# GD32FxxxR-dev-board.net
KiCad netlist of a schematic drawn in EAGLE
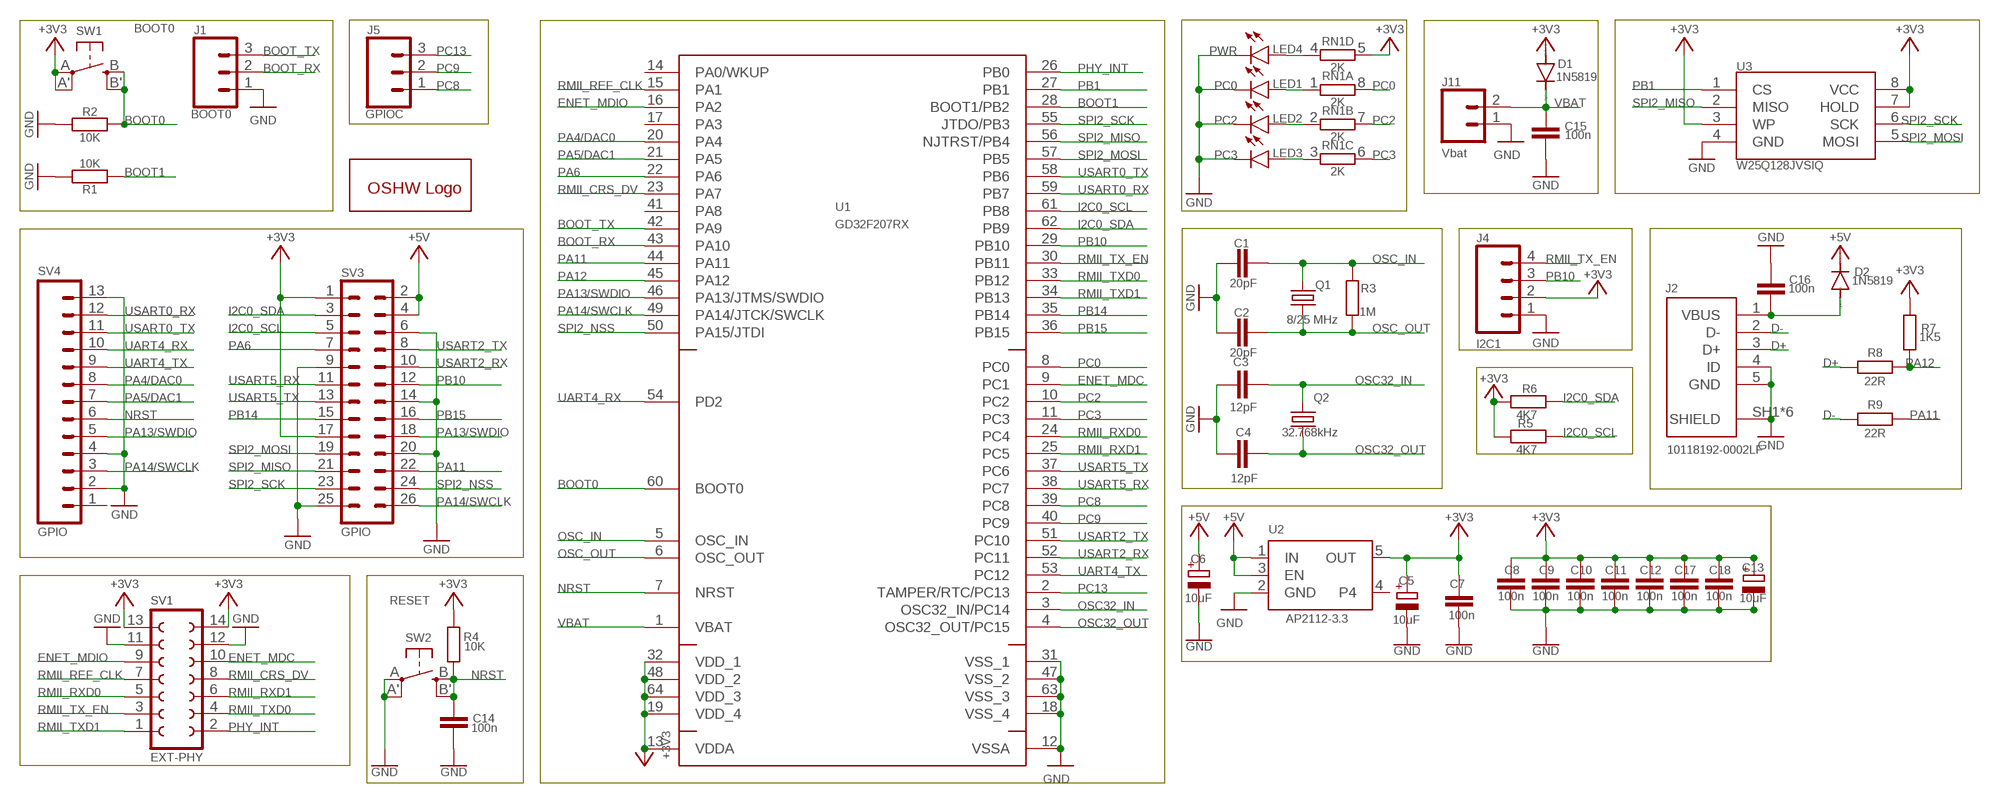
[diagram p0: schematic, sheet 1]

(export (version "E")
  (design (tool "Eeschema 10.0.6"))
  (components
    (comp (ref "C1")
      (value "20pF")
      (footprint "eagle-import:C0603")
      (libsource (lib "eagle-import") (part "C-EUC0603"))
    )
    (comp (ref "C2")
      (value "20pF")
      (footprint "eagle-import:C0603")
      (libsource (lib "eagle-import") (part "C-EUC0603"))
    )
    (comp (ref "C3")
      (value "12pF")
      (footprint "eagle-import:C0603")
      (libsource (lib "eagle-import") (part "C-EUC0603"))
    )
    (comp (ref "C4")
      (value "12pF")
      (footprint "eagle-import:C0603")
      (libsource (lib "eagle-import") (part "C-EUC0603"))
    )
    (comp (ref "C5")
      (value "10uF")
      (footprint "eagle-import:A_3216-18R")
      (libsource (lib "eagle-import") (part "CPOL-EUA/3216-18R"))
    )
    (comp (ref "C6")
      (value "10uF")
      (footprint "eagle-import:A_3216-18R")
      (libsource (lib "eagle-import") (part "CPOL-EUA/3216-18R"))
    )
    (comp (ref "C7")
      (value "100n")
      (footprint "eagle-import:C0603")
      (libsource (lib "eagle-import") (part "C-EUC0603"))
    )
    (comp (ref "C8")
      (value "100n")
      (footprint "eagle-import:C0603")
      (libsource (lib "eagle-import") (part "C-EUC0603"))
    )
    (comp (ref "C9")
      (value "100n")
      (footprint "eagle-import:C0603")
      (libsource (lib "eagle-import") (part "C-EUC0603"))
    )
    (comp (ref "C10")
      (value "100n")
      (footprint "eagle-import:C0603")
      (libsource (lib "eagle-import") (part "C-EUC0603"))
    )
    (comp (ref "C11")
      (value "100n")
      (footprint "eagle-import:C0603")
      (libsource (lib "eagle-import") (part "C-EUC0603"))
    )
    (comp (ref "C12")
      (value "100n")
      (footprint "eagle-import:C0603")
      (libsource (lib "eagle-import") (part "C-EUC0603"))
    )
    (comp (ref "C13")
      (value "10uF")
      (footprint "eagle-import:A_3216-18R")
      (libsource (lib "eagle-import") (part "CPOL-EUA/3216-18R"))
    )
    (comp (ref "C14")
      (value "100n")
      (footprint "eagle-import:C0603")
      (libsource (lib "eagle-import") (part "C-EUC0603"))
    )
    (comp (ref "C15")
      (value "100n")
      (footprint "eagle-import:C0603")
      (libsource (lib "eagle-import") (part "C-EUC0603"))
    )
    (comp (ref "C16")
      (value "100n")
      (footprint "eagle-import:C0603")
      (libsource (lib "eagle-import") (part "C-EUC0603"))
    )
    (comp (ref "C17")
      (value "100n")
      (footprint "eagle-import:C0603")
      (libsource (lib "eagle-import") (part "C-EUC0603"))
    )
    (comp (ref "C18")
      (value "100n")
      (footprint "eagle-import:C0603")
      (libsource (lib "eagle-import") (part "C-EUC0603"))
    )
    (comp (ref "D1")
      (value "1N5819")
      (footprint "eagle-import:SOD323-R")
      (libsource (lib "eagle-import") (part "DIODE-SOD323-R"))
    )
    (comp (ref "D2")
      (value "1N5819")
      (footprint "eagle-import:SOD323-R")
      (libsource (lib "eagle-import") (part "DIODE-SOD323-R"))
    )
    (comp (ref "GOLD_ORB_SM1")
      (value "OSHWLOGOLOGO5MM")
      (footprint "eagle-import:OSHW_5MM")
      (libsource (lib "eagle-import") (part "OSHWLOGOLOGO5MM"))
    )
    (comp (ref "J1")
      (value "BOOT0")
      (footprint "eagle-import:1X03")
      (libsource (lib "eagle-import") (part "CONN_03"))
    )
    (comp (ref "J2")
      (value "10118192-0002LF")
      (footprint "eagle-import:10118192-0002LF")
      (fields
        (field (name "DIGIKEY_PARTNO") "609-5379-2-ND")
        (field (name "MANUFACTURER") "Amphenol ICC (FCI)")
        (field (name "CREATED_BY") "PCBLayout.com")
      )
      (libsource (lib "eagle-import") (part "10118192-0002LF"))
    )
    (comp (ref "J4")
      (value "I2C1")
      (footprint "eagle-import:1X04")
      (libsource (lib "eagle-import") (part "CONN_04"))
    )
    (comp (ref "J5")
      (value "GPIOC")
      (footprint "eagle-import:1X03")
      (libsource (lib "eagle-import") (part "CONN_03"))
    )
    (comp (ref "J11")
      (value "Vbat")
      (footprint "eagle-import:1X02_NO_SILK")
      (libsource (lib "eagle-import") (part "CONN_021X02_NO_SILK"))
    )
    (comp (ref "LED1")
      (value "PC0")
      (footprint "eagle-import:CHIP-LED0603")
      (libsource (lib "eagle-import") (part "LEDCHIP-LED0603"))
    )
    (comp (ref "LED2")
      (value "PC2")
      (footprint "eagle-import:CHIP-LED0603")
      (libsource (lib "eagle-import") (part "LEDCHIP-LED0603"))
    )
    (comp (ref "LED3")
      (value "PC3")
      (footprint "eagle-import:CHIP-LED0603")
      (libsource (lib "eagle-import") (part "LEDCHIP-LED0603"))
    )
    (comp (ref "LED4")
      (value "PWR")
      (footprint "eagle-import:CHIP-LED0603")
      (libsource (lib "eagle-import") (part "LEDCHIP-LED0603"))
    )
    (comp (ref "Q1")
      (value "8/25 MHz")
      (footprint "eagle-import:CSM-7X-DU")
      (libsource (lib "eagle-import") (part "CSM-7X-DU"))
    )
    (comp (ref "Q2")
      (value "32.768kHz")
      (footprint "eagle-import:3.2X1.5")
      (libsource (lib "eagle-import") (part "KX-327-NHT"))
    )
    (comp (ref "R1")
      (value "10K")
      (footprint "eagle-import:R0603")
      (libsource (lib "eagle-import") (part "R-EU_R0603"))
    )
    (comp (ref "R2")
      (value "10K")
      (footprint "eagle-import:R0603")
      (libsource (lib "eagle-import") (part "R-EU_R0603"))
    )
    (comp (ref "R3")
      (value "1M")
      (footprint "eagle-import:R0603")
      (libsource (lib "eagle-import") (part "R-EU_R0603"))
    )
    (comp (ref "R4")
      (value "10K")
      (footprint "eagle-import:R0603")
      (libsource (lib "eagle-import") (part "R-EU_R0603"))
    )
    (comp (ref "R5")
      (value "4K7")
      (footprint "eagle-import:R0603")
      (libsource (lib "eagle-import") (part "R-EU_R0603"))
    )
    (comp (ref "R6")
      (value "4K7")
      (footprint "eagle-import:R0603")
      (libsource (lib "eagle-import") (part "R-EU_R0603"))
    )
    (comp (ref "R7")
      (value "1K5")
      (footprint "eagle-import:R0603")
      (libsource (lib "eagle-import") (part "R-EU_R0603"))
    )
    (comp (ref "R8")
      (value "22R")
      (footprint "eagle-import:R0603")
      (libsource (lib "eagle-import") (part "R-EU_R0603"))
    )
    (comp (ref "R9")
      (value "22R")
      (footprint "eagle-import:R0603")
      (libsource (lib "eagle-import") (part "R-EU_R0603"))
    )
    (comp (ref "RN1")
      (value "2K")
      (footprint "eagle-import:4X0402ARV341")
      (fields (field (name "JLCPCB") "C44891"))
      (libsource (lib "eagle-import") (part "4R-N0402ARV341"))
    )
    (comp (ref "SV1")
      (value "EXT-PHY")
      (footprint "eagle-import:FE07-2W")
      (libsource (lib "eagle-import") (part "FE07-2W"))
    )
    (comp (ref "SV3")
      (value "GPIO")
      (footprint "eagle-import:MA13-2")
      (libsource (lib "eagle-import") (part "MA13-2"))
    )
    (comp (ref "SV4")
      (value "GPIO")
      (footprint "eagle-import:1X13")
      (libsource (lib "eagle-import") (part "CONN_13"))
    )
    (comp (ref "SW1")
      (value "BOOT0")
      (footprint "eagle-import:EVQ-Q2")
      (libsource (lib "eagle-import") (part "SPST_TACT-EVQQ2"))
    )
    (comp (ref "SW2")
      (value "RESET")
      (footprint "eagle-import:EVQ-Q2")
      (libsource (lib "eagle-import") (part "SPST_TACT-EVQQ2"))
    )
    (comp (ref "U1")
      (value "GD32F207RX")
      (footprint "eagle-import:LQFP64")
      (libsource (lib "eagle-import") (part "GD32F207RX"))
    )
    (comp (ref "U2")
      (value "AP2112-3.3")
      (footprint "eagle-import:SOT23-5")
      (libsource (lib "eagle-import") (part "VREG_SOT23-5"))
    )
    (comp (ref "U3")
      (value "W25Q128JVSIQ")
      (footprint "eagle-import:SO08-EIAJ")
      (libsource (lib "eagle-import") (part "SPI_FLASH-X25XXSMD1"))
    )
  )
  (nets
    (net (code "1") (name "+3V3") (class "Default")
      (node (ref "C10") (pin "1") (pinfunction "1_1") (pintype "passive"))
      (node (ref "C11") (pin "1") (pinfunction "1_1") (pintype "passive"))
      (node (ref "C12") (pin "1") (pinfunction "1_1") (pintype "passive"))
      (node (ref "C13") (pin "+") (pinfunction "+_+") (pintype "passive"))
      (node (ref "C17") (pin "1") (pinfunction "1_1") (pintype "passive"))
      (node (ref "C18") (pin "1") (pinfunction "1_1") (pintype "passive"))
      (node (ref "C5") (pin "+") (pinfunction "+_+") (pintype "passive"))
      (node (ref "C7") (pin "1") (pinfunction "1_1") (pintype "passive"))
      (node (ref "C8") (pin "1") (pinfunction "1_1") (pintype "passive"))
      (node (ref "C9") (pin "1") (pinfunction "1_1") (pintype "passive"))
      (node (ref "D1") (pin "A") (pinfunction "A_A") (pintype "passive"))
      (node (ref "J4") (pin "2") (pinfunction "2_2") (pintype "passive"))
      (node (ref "R4") (pin "2") (pinfunction "2_2") (pintype "passive"))
      (node (ref "R5") (pin "2") (pinfunction "2_2") (pintype "passive"))
      (node (ref "R6") (pin "2") (pinfunction "2_2") (pintype "passive"))
      (node (ref "R7") (pin "2") (pinfunction "2_2") (pintype "passive"))
      (node (ref "RN1") (pin "5") (pinfunction "2_5") (pintype "passive"))
      (node (ref "SV1") (pin "13") (pinfunction "13_13") (pintype "passive"))
      (node (ref "SV1") (pin "14") (pinfunction "14_14") (pintype "passive"))
      (node (ref "SV3") (pin "1") (pinfunction "1_1") (pintype "passive"))
      (node (ref "SV3") (pin "17") (pinfunction "17_17") (pintype "passive"))
      (node (ref "SW1") (pin "A") (pinfunction "P_A") (pintype "passive"))
      (node (ref "SW1") (pin "A'") (pinfunction "P1_A'") (pintype "passive"))
      (node (ref "U1") (pin "13") (pinfunction "VDDA_13") (pintype "power_in"))
      (node (ref "U1") (pin "19") (pinfunction "VDD_4_19") (pintype "power_in"))
      (node (ref "U1") (pin "32") (pinfunction "VDD_1_32") (pintype "power_in"))
      (node (ref "U1") (pin "48") (pinfunction "VDD_2_48") (pintype "power_in"))
      (node (ref "U1") (pin "64") (pinfunction "VDD_3_64") (pintype "power_in"))
      (node (ref "U2") (pin "5") (pinfunction "OUT_5") (pintype "power_in"))
      (node (ref "U3") (pin "3") (pinfunction "WP_3") (pintype "bidirectional"))
      (node (ref "U3") (pin "7") (pinfunction "HOLD_7") (pintype "bidirectional"))
      (node (ref "U3") (pin "8") (pinfunction "VCC_8") (pintype "power_in"))
    )
    (net (code "2") (name "+5V") (class "Default")
      (node (ref "C6") (pin "+") (pinfunction "+_+") (pintype "passive"))
      (node (ref "D2") (pin "C") (pinfunction "C_C") (pintype "passive"))
      (node (ref "SV3") (pin "2") (pinfunction "2_2") (pintype "passive"))
      (node (ref "SV3") (pin "4") (pinfunction "4_4") (pintype "passive"))
      (node (ref "U2") (pin "1") (pinfunction "IN_1") (pintype "power_in"))
      (node (ref "U2") (pin "3") (pinfunction "EN_3") (pintype "input"))
    )
    (net (code "3") (name "/BOOT0") (class "Default")
      (node (ref "R2") (pin "2") (pinfunction "2_2") (pintype "passive"))
      (node (ref "SW1") (pin "B") (pinfunction "S_B") (pintype "passive"))
      (node (ref "SW1") (pin "B'") (pinfunction "S1_B'") (pintype "passive"))
      (node (ref "U1") (pin "60") (pinfunction "BOOT0_60") (pintype "bidirectional"))
    )
    (net (code "4") (name "/BOOT1") (class "Default")
      (node (ref "R1") (pin "1") (pinfunction "1_1") (pintype "passive"))
      (node (ref "U1") (pin "28") (pinfunction "BOOT1/PB2_28") (pintype "bidirectional"))
    )
    (net (code "5") (name "/BOOT_RX") (class "Default")
      (node (ref "J1") (pin "2") (pinfunction "2_2") (pintype "passive"))
      (node (ref "U1") (pin "43") (pinfunction "PA10_43") (pintype "bidirectional"))
    )
    (net (code "6") (name "/BOOT_TX") (class "Default")
      (node (ref "J1") (pin "3") (pinfunction "3_3") (pintype "passive"))
      (node (ref "U1") (pin "42") (pinfunction "PA9_42") (pintype "bidirectional"))
    )
    (net (code "7") (name "/D+") (class "Default")
      (node (ref "J2") (pin "3") (pinfunction "D+_3") (pintype "passive"))
      (node (ref "R8") (pin "1") (pinfunction "1_1") (pintype "passive"))
    )
    (net (code "8") (name "/D-") (class "Default")
      (node (ref "J2") (pin "2") (pinfunction "D-_2") (pintype "passive"))
      (node (ref "R9") (pin "1") (pinfunction "1_1") (pintype "passive"))
    )
    (net (code "9") (name "/ENET_MDC") (class "Default")
      (node (ref "SV1") (pin "10") (pinfunction "10_10") (pintype "passive"))
      (node (ref "U1") (pin "9") (pinfunction "PC1_9") (pintype "bidirectional"))
    )
    (net (code "10") (name "/ENET_MDIO") (class "Default")
      (node (ref "SV1") (pin "9") (pinfunction "9_9") (pintype "passive"))
      (node (ref "U1") (pin "16") (pinfunction "PA2_16") (pintype "bidirectional"))
    )
    (net (code "11") (name "/I2C0_SCL") (class "Default")
      (node (ref "R5") (pin "1") (pinfunction "1_1") (pintype "passive"))
      (node (ref "SV3") (pin "5") (pinfunction "5_5") (pintype "passive"))
      (node (ref "U1") (pin "61") (pinfunction "PB8_61") (pintype "bidirectional"))
    )
    (net (code "12") (name "/I2C0_SDA") (class "Default")
      (node (ref "R6") (pin "1") (pinfunction "1_1") (pintype "passive"))
      (node (ref "SV3") (pin "3") (pinfunction "3_3") (pintype "passive"))
      (node (ref "U1") (pin "62") (pinfunction "PB9_62") (pintype "bidirectional"))
    )
    (net (code "13") (name "/NRST") (class "Default")
      (node (ref "C14") (pin "1") (pinfunction "1_1") (pintype "passive"))
      (node (ref "R4") (pin "1") (pinfunction "1_1") (pintype "passive"))
      (node (ref "SV4") (pin "6") (pinfunction "6_6") (pintype "passive"))
      (node (ref "SW2") (pin "B") (pinfunction "S_B") (pintype "passive"))
      (node (ref "SW2") (pin "B'") (pinfunction "S1_B'") (pintype "passive"))
      (node (ref "U1") (pin "7") (pinfunction "NRST_7") (pintype "power_in"))
    )
    (net (code "14") (name "/OSC32_IN") (class "Default")
      (node (ref "C3") (pin "2") (pinfunction "2_2") (pintype "passive"))
      (node (ref "Q2") (pin "2") (pinfunction "2_2") (pintype "passive"))
      (node (ref "U1") (pin "3") (pinfunction "OSC32_IN/PC14_3") (pintype "bidirectional"))
    )
    (net (code "15") (name "/OSC32_OUT") (class "Default")
      (node (ref "C4") (pin "2") (pinfunction "2_2") (pintype "passive"))
      (node (ref "Q2") (pin "1") (pinfunction "1_1") (pintype "passive"))
      (node (ref "U1") (pin "4") (pinfunction "OSC32_OUT/PC15_4") (pintype "bidirectional"))
    )
    (net (code "16") (name "/OSC_IN") (class "Default")
      (node (ref "C1") (pin "2") (pinfunction "2_2") (pintype "passive"))
      (node (ref "Q1") (pin "2") (pinfunction "2_2") (pintype "passive"))
      (node (ref "R3") (pin "1") (pinfunction "1_1") (pintype "passive"))
      (node (ref "U1") (pin "5") (pinfunction "OSC_IN_5") (pintype "bidirectional"))
    )
    (net (code "17") (name "/OSC_OUT") (class "Default")
      (node (ref "C2") (pin "2") (pinfunction "2_2") (pintype "passive"))
      (node (ref "Q1") (pin "1") (pinfunction "1_1") (pintype "passive"))
      (node (ref "R3") (pin "2") (pinfunction "2_2") (pintype "passive"))
      (node (ref "U1") (pin "6") (pinfunction "OSC_OUT_6") (pintype "bidirectional"))
    )
    (net (code "18") (name "/PA4{slash}DAC0") (class "Default")
      (node (ref "SV4") (pin "8") (pinfunction "8_8") (pintype "passive"))
      (node (ref "U1") (pin "20") (pinfunction "PA4_20") (pintype "bidirectional"))
    )
    (net (code "19") (name "/PA5{slash}DAC1") (class "Default")
      (node (ref "SV4") (pin "7") (pinfunction "7_7") (pintype "passive"))
      (node (ref "U1") (pin "21") (pinfunction "PA5_21") (pintype "bidirectional"))
    )
    (net (code "20") (name "/PA6") (class "Default")
      (node (ref "SV3") (pin "7") (pinfunction "7_7") (pintype "passive"))
      (node (ref "U1") (pin "22") (pinfunction "PA6_22") (pintype "bidirectional"))
    )
    (net (code "21") (name "/PA11") (class "Default")
      (node (ref "R9") (pin "2") (pinfunction "2_2") (pintype "passive"))
      (node (ref "SV3") (pin "22") (pinfunction "22_22") (pintype "passive"))
      (node (ref "U1") (pin "44") (pinfunction "PA11_44") (pintype "bidirectional"))
    )
    (net (code "22") (name "/PA12") (class "Default")
      (node (ref "R7") (pin "1") (pinfunction "1_1") (pintype "passive"))
      (node (ref "R8") (pin "2") (pinfunction "2_2") (pintype "passive"))
      (node (ref "U1") (pin "45") (pinfunction "PA12_45") (pintype "bidirectional"))
    )
    (net (code "23") (name "/PA13{slash}SWDIO") (class "Default")
      (node (ref "SV3") (pin "18") (pinfunction "18_18") (pintype "passive"))
      (node (ref "SV4") (pin "5") (pinfunction "5_5") (pintype "passive"))
      (node (ref "U1") (pin "46") (pinfunction "PA13/JTMS/SWDIO_46") (pintype "bidirectional"))
    )
    (net (code "24") (name "/PA14{slash}SWCLK") (class "Default")
      (node (ref "SV3") (pin "26") (pinfunction "26_26") (pintype "passive"))
      (node (ref "SV4") (pin "3") (pinfunction "3_3") (pintype "passive"))
      (node (ref "U1") (pin "49") (pinfunction "PA14/JTCK/SWCLK_49") (pintype "bidirectional"))
    )
    (net (code "25") (name "/PB1") (class "Default")
      (node (ref "U1") (pin "27") (pinfunction "PB1_27") (pintype "bidirectional"))
      (node (ref "U3") (pin "1") (pinfunction "CS_1") (pintype "bidirectional"))
    )
    (net (code "26") (name "/PB10") (class "Default")
      (node (ref "J4") (pin "3") (pinfunction "3_3") (pintype "passive"))
      (node (ref "SV3") (pin "12") (pinfunction "12_12") (pintype "passive"))
      (node (ref "U1") (pin "29") (pinfunction "PB10_29") (pintype "bidirectional"))
    )
    (net (code "27") (name "/PB14") (class "Default")
      (node (ref "SV3") (pin "15") (pinfunction "15_15") (pintype "passive"))
      (node (ref "U1") (pin "35") (pinfunction "PB14_35") (pintype "bidirectional"))
    )
    (net (code "28") (name "/PB15") (class "Default")
      (node (ref "SV3") (pin "16") (pinfunction "16_16") (pintype "passive"))
      (node (ref "U1") (pin "36") (pinfunction "PB15_36") (pintype "bidirectional"))
    )
    (net (code "29") (name "/PC0") (class "Default")
      (node (ref "RN1") (pin "8") (pinfunction "2_8") (pintype "passive"))
      (node (ref "U1") (pin "8") (pinfunction "PC0_8") (pintype "bidirectional"))
    )
    (net (code "30") (name "/PC2") (class "Default")
      (node (ref "RN1") (pin "7") (pinfunction "2_7") (pintype "passive"))
      (node (ref "U1") (pin "10") (pinfunction "PC2_10") (pintype "bidirectional"))
    )
    (net (code "31") (name "/PC3") (class "Default")
      (node (ref "RN1") (pin "6") (pinfunction "2_6") (pintype "passive"))
      (node (ref "U1") (pin "11") (pinfunction "PC3_11") (pintype "bidirectional"))
    )
    (net (code "32") (name "/PC8") (class "Default")
      (node (ref "J5") (pin "1") (pinfunction "1_1") (pintype "passive"))
      (node (ref "U1") (pin "39") (pinfunction "PC8_39") (pintype "bidirectional"))
    )
    (net (code "33") (name "/PC9") (class "Default")
      (node (ref "J5") (pin "2") (pinfunction "2_2") (pintype "passive"))
      (node (ref "U1") (pin "40") (pinfunction "PC9_40") (pintype "bidirectional"))
    )
    (net (code "34") (name "/PC13") (class "Default")
      (node (ref "J5") (pin "3") (pinfunction "3_3") (pintype "passive"))
      (node (ref "U1") (pin "2") (pinfunction "TAMPER/RTC/PC13_2") (pintype "bidirectional"))
    )
    (net (code "35") (name "/PHY_INT") (class "Default")
      (node (ref "SV1") (pin "2") (pinfunction "2_2") (pintype "passive"))
      (node (ref "U1") (pin "26") (pinfunction "PB0_26") (pintype "bidirectional"))
    )
    (net (code "36") (name "/RMII_CRS_DV") (class "Default")
      (node (ref "SV1") (pin "8") (pinfunction "8_8") (pintype "passive"))
      (node (ref "U1") (pin "23") (pinfunction "PA7_23") (pintype "bidirectional"))
    )
    (net (code "37") (name "/RMII_REF_CLK") (class "Default")
      (node (ref "SV1") (pin "7") (pinfunction "7_7") (pintype "passive"))
      (node (ref "U1") (pin "15") (pinfunction "PA1_15") (pintype "bidirectional"))
    )
    (net (code "38") (name "/RMII_RXD0") (class "Default")
      (node (ref "SV1") (pin "5") (pinfunction "5_5") (pintype "passive"))
      (node (ref "U1") (pin "24") (pinfunction "PC4_24") (pintype "bidirectional"))
    )
    (net (code "39") (name "/RMII_RXD1") (class "Default")
      (node (ref "SV1") (pin "6") (pinfunction "6_6") (pintype "passive"))
      (node (ref "U1") (pin "25") (pinfunction "PC5_25") (pintype "bidirectional"))
    )
    (net (code "40") (name "/RMII_TXD0") (class "Default")
      (node (ref "SV1") (pin "4") (pinfunction "4_4") (pintype "passive"))
      (node (ref "U1") (pin "33") (pinfunction "PB12_33") (pintype "bidirectional"))
    )
    (net (code "41") (name "/RMII_TXD1") (class "Default")
      (node (ref "SV1") (pin "1") (pinfunction "1_1") (pintype "passive"))
      (node (ref "U1") (pin "34") (pinfunction "PB13_34") (pintype "bidirectional"))
    )
    (net (code "42") (name "/RMII_TX_EN") (class "Default")
      (node (ref "J4") (pin "4") (pinfunction "4_4") (pintype "passive"))
      (node (ref "SV1") (pin "3") (pinfunction "3_3") (pintype "passive"))
      (node (ref "U1") (pin "30") (pinfunction "PB11_30") (pintype "bidirectional"))
    )
    (net (code "43") (name "/SPI2_MISO") (class "Default")
      (node (ref "SV3") (pin "21") (pinfunction "21_21") (pintype "passive"))
      (node (ref "U1") (pin "56") (pinfunction "NJTRST/PB4_56") (pintype "bidirectional"))
      (node (ref "U3") (pin "2") (pinfunction "MISO_2") (pintype "bidirectional"))
    )
    (net (code "44") (name "/SPI2_MOSI") (class "Default")
      (node (ref "SV3") (pin "19") (pinfunction "19_19") (pintype "passive"))
      (node (ref "U1") (pin "57") (pinfunction "PB5_57") (pintype "bidirectional"))
      (node (ref "U3") (pin "5") (pinfunction "MOSI_5") (pintype "bidirectional"))
    )
    (net (code "45") (name "/SPI2_NSS") (class "Default")
      (node (ref "SV3") (pin "24") (pinfunction "24_24") (pintype "passive"))
      (node (ref "U1") (pin "50") (pinfunction "PA15/JTDI_50") (pintype "bidirectional"))
    )
    (net (code "46") (name "/SPI2_SCK") (class "Default")
      (node (ref "SV3") (pin "23") (pinfunction "23_23") (pintype "passive"))
      (node (ref "U1") (pin "55") (pinfunction "JTDO/PB3_55") (pintype "bidirectional"))
      (node (ref "U3") (pin "6") (pinfunction "SCK_6") (pintype "bidirectional"))
    )
    (net (code "47") (name "/UART4_RX") (class "Default")
      (node (ref "SV4") (pin "10") (pinfunction "10_10") (pintype "passive"))
      (node (ref "U1") (pin "54") (pinfunction "PD2_54") (pintype "bidirectional"))
    )
    (net (code "48") (name "/UART4_TX") (class "Default")
      (node (ref "SV4") (pin "9") (pinfunction "9_9") (pintype "passive"))
      (node (ref "U1") (pin "53") (pinfunction "PC12_53") (pintype "bidirectional"))
    )
    (net (code "49") (name "/USART0_RX") (class "Default")
      (node (ref "SV4") (pin "12") (pinfunction "12_12") (pintype "passive"))
      (node (ref "U1") (pin "59") (pinfunction "PB7_59") (pintype "bidirectional"))
    )
    (net (code "50") (name "/USART0_TX") (class "Default")
      (node (ref "SV4") (pin "11") (pinfunction "11_11") (pintype "passive"))
      (node (ref "U1") (pin "58") (pinfunction "PB6_58") (pintype "bidirectional"))
    )
    (net (code "51") (name "/USART2_RX") (class "Default")
      (node (ref "SV3") (pin "10") (pinfunction "10_10") (pintype "passive"))
      (node (ref "U1") (pin "52") (pinfunction "PC11_52") (pintype "bidirectional"))
    )
    (net (code "52") (name "/USART2_TX") (class "Default")
      (node (ref "SV3") (pin "8") (pinfunction "8_8") (pintype "passive"))
      (node (ref "U1") (pin "51") (pinfunction "PC10_51") (pintype "bidirectional"))
    )
    (net (code "53") (name "/USART5_RX") (class "Default")
      (node (ref "SV3") (pin "11") (pinfunction "11_11") (pintype "passive"))
      (node (ref "U1") (pin "38") (pinfunction "PC7_38") (pintype "bidirectional"))
    )
    (net (code "54") (name "/USART5_TX") (class "Default")
      (node (ref "SV3") (pin "13") (pinfunction "13_13") (pintype "passive"))
      (node (ref "U1") (pin "37") (pinfunction "PC6_37") (pintype "bidirectional"))
    )
    (net (code "55") (name "/VBAT") (class "Default")
      (node (ref "C15") (pin "1") (pinfunction "1_1") (pintype "passive"))
      (node (ref "D1") (pin "C") (pinfunction "C_C") (pintype "passive"))
      (node (ref "J11") (pin "2") (pinfunction "2_2") (pintype "passive"))
      (node (ref "U1") (pin "1") (pinfunction "VBAT_1") (pintype "power_in"))
    )
    (net (code "56") (name "GND") (class "Default")
      (node (ref "C1") (pin "1") (pinfunction "1_1") (pintype "passive"))
      (node (ref "C10") (pin "2") (pinfunction "2_2") (pintype "passive"))
      (node (ref "C11") (pin "2") (pinfunction "2_2") (pintype "passive"))
      (node (ref "C12") (pin "2") (pinfunction "2_2") (pintype "passive"))
      (node (ref "C13") (pin "-") (pinfunction "-_-") (pintype "passive"))
      (node (ref "C14") (pin "2") (pinfunction "2_2") (pintype "passive"))
      (node (ref "C15") (pin "2") (pinfunction "2_2") (pintype "passive"))
      (node (ref "C16") (pin "1") (pinfunction "1_1") (pintype "passive"))
      (node (ref "C17") (pin "2") (pinfunction "2_2") (pintype "passive"))
      (node (ref "C18") (pin "2") (pinfunction "2_2") (pintype "passive"))
      (node (ref "C2") (pin "1") (pinfunction "1_1") (pintype "passive"))
      (node (ref "C3") (pin "1") (pinfunction "1_1") (pintype "passive"))
      (node (ref "C4") (pin "1") (pinfunction "1_1") (pintype "passive"))
      (node (ref "C5") (pin "-") (pinfunction "-_-") (pintype "passive"))
      (node (ref "C6") (pin "-") (pinfunction "-_-") (pintype "passive"))
      (node (ref "C7") (pin "2") (pinfunction "2_2") (pintype "passive"))
      (node (ref "C8") (pin "2") (pinfunction "2_2") (pintype "passive"))
      (node (ref "C9") (pin "2") (pinfunction "2_2") (pintype "passive"))
      (node (ref "J1") (pin "1") (pinfunction "1_1") (pintype "passive"))
      (node (ref "J11") (pin "1") (pinfunction "1_1") (pintype "passive"))
      (node (ref "J2") (pin "4") (pinfunction "ID_4") (pintype "passive"))
      (node (ref "J2") (pin "5") (pinfunction "GND_5") (pintype "passive"))
      (node (ref "J2") (pin "SH1") (pinfunction "SHIELD_SH1") (pintype "power_in"))
      (node (ref "J2") (pin "SH2") (pinfunction "SHIELD_SH2") (pintype "power_in"))
      (node (ref "J2") (pin "SH3") (pinfunction "SHIELD_SH3") (pintype "power_in"))
      (node (ref "J2") (pin "SH4") (pinfunction "SHIELD_SH4") (pintype "power_in"))
      (node (ref "J2") (pin "SH5") (pinfunction "SHIELD_SH5") (pintype "power_in"))
      (node (ref "J2") (pin "SH6") (pinfunction "SHIELD_SH6") (pintype "power_in"))
      (node (ref "J4") (pin "1") (pinfunction "1_1") (pintype "passive"))
      (node (ref "LED1") (pin "C") (pinfunction "C_C") (pintype "passive"))
      (node (ref "LED2") (pin "C") (pinfunction "C_C") (pintype "passive"))
      (node (ref "LED3") (pin "C") (pinfunction "C_C") (pintype "passive"))
      (node (ref "LED4") (pin "C") (pinfunction "C_C") (pintype "passive"))
      (node (ref "R1") (pin "2") (pinfunction "2_2") (pintype "passive"))
      (node (ref "R2") (pin "1") (pinfunction "1_1") (pintype "passive"))
      (node (ref "SV1") (pin "11") (pinfunction "11_11") (pintype "passive"))
      (node (ref "SV1") (pin "12") (pinfunction "12_12") (pintype "passive"))
      (node (ref "SV3") (pin "14") (pinfunction "14_14") (pintype "passive"))
      (node (ref "SV3") (pin "20") (pinfunction "20_20") (pintype "passive"))
      (node (ref "SV3") (pin "25") (pinfunction "25_25") (pintype "passive"))
      (node (ref "SV3") (pin "6") (pinfunction "6_6") (pintype "passive"))
      (node (ref "SV3") (pin "9") (pinfunction "9_9") (pintype "passive"))
      (node (ref "SV4") (pin "13") (pinfunction "13_13") (pintype "passive"))
      (node (ref "SV4") (pin "2") (pinfunction "2_2") (pintype "passive"))
      (node (ref "SV4") (pin "4") (pinfunction "4_4") (pintype "passive"))
      (node (ref "SW2") (pin "A") (pinfunction "P_A") (pintype "passive"))
      (node (ref "SW2") (pin "A'") (pinfunction "P1_A'") (pintype "passive"))
      (node (ref "U1") (pin "12") (pinfunction "VSSA_12") (pintype "power_in"))
      (node (ref "U1") (pin "18") (pinfunction "VSS_4_18") (pintype "power_in"))
      (node (ref "U1") (pin "31") (pinfunction "VSS_1_31") (pintype "power_in"))
      (node (ref "U1") (pin "47") (pinfunction "VSS_2_47") (pintype "power_in"))
      (node (ref "U1") (pin "63") (pinfunction "VSS_3_63") (pintype "power_in"))
      (node (ref "U2") (pin "2") (pinfunction "GND_2") (pintype "power_in"))
      (node (ref "U3") (pin "4") (pinfunction "GND_4") (pintype "power_in"))
    )
    (net (code "57") (name "Net-(J2-VBUS)") (class "Default")
      (node (ref "C16") (pin "2") (pinfunction "2_2") (pintype "passive"))
      (node (ref "D2") (pin "A") (pinfunction "A_A") (pintype "passive"))
      (node (ref "J2") (pin "1") (pinfunction "VBUS_1") (pintype "passive"))
    )
    (net (code "58") (name "Net-(LED1-PadA)") (class "Default")
      (node (ref "LED1") (pin "A") (pinfunction "A_A") (pintype "passive"))
      (node (ref "RN1") (pin "1") (pinfunction "1_1") (pintype "passive"))
    )
    (net (code "59") (name "Net-(RN1B-1)") (class "Default")
      (node (ref "LED2") (pin "A") (pinfunction "A_A") (pintype "passive"))
      (node (ref "RN1") (pin "2") (pinfunction "1_2") (pintype "passive"))
    )
    (net (code "60") (name "Net-(RN1C-1)") (class "Default")
      (node (ref "LED3") (pin "A") (pinfunction "A_A") (pintype "passive"))
      (node (ref "RN1") (pin "3") (pinfunction "1_3") (pintype "passive"))
    )
    (net (code "61") (name "Net-(RN1D-1)") (class "Default")
      (node (ref "LED4") (pin "A") (pinfunction "A_A") (pintype "passive"))
      (node (ref "RN1") (pin "4") (pinfunction "1_4") (pintype "passive"))
    )
    (net (code "62") (name "unconnected-(SV4-Pad1)") (class "Default")
      (node (ref "SV4") (pin "1") (pinfunction "1_1") (pintype "passive"))
    )
    (net (code "63") (name "unconnected-(U1-PA0{slash}WKUP-Pad14)") (class "Default")
      (node (ref "U1") (pin "14") (pinfunction "PA0/WKUP_14") (pintype "bidirectional"))
    )
    (net (code "64") (name "unconnected-(U1-PA3-Pad17)") (class "Default")
      (node (ref "U1") (pin "17") (pinfunction "PA3_17") (pintype "bidirectional"))
    )
    (net (code "65") (name "unconnected-(U1-PA8-Pad41)") (class "Default")
      (node (ref "U1") (pin "41") (pinfunction "PA8_41") (pintype "bidirectional"))
    )
    (net (code "66") (name "unconnected-(U2-P4-Pad4)") (class "Default")
      (node (ref "U2") (pin "4") (pinfunction "P4_4") (pintype "bidirectional"))
    )
  )
)
